# sensor.net
KiCad netlist of a schematic drawn in Altium Designer
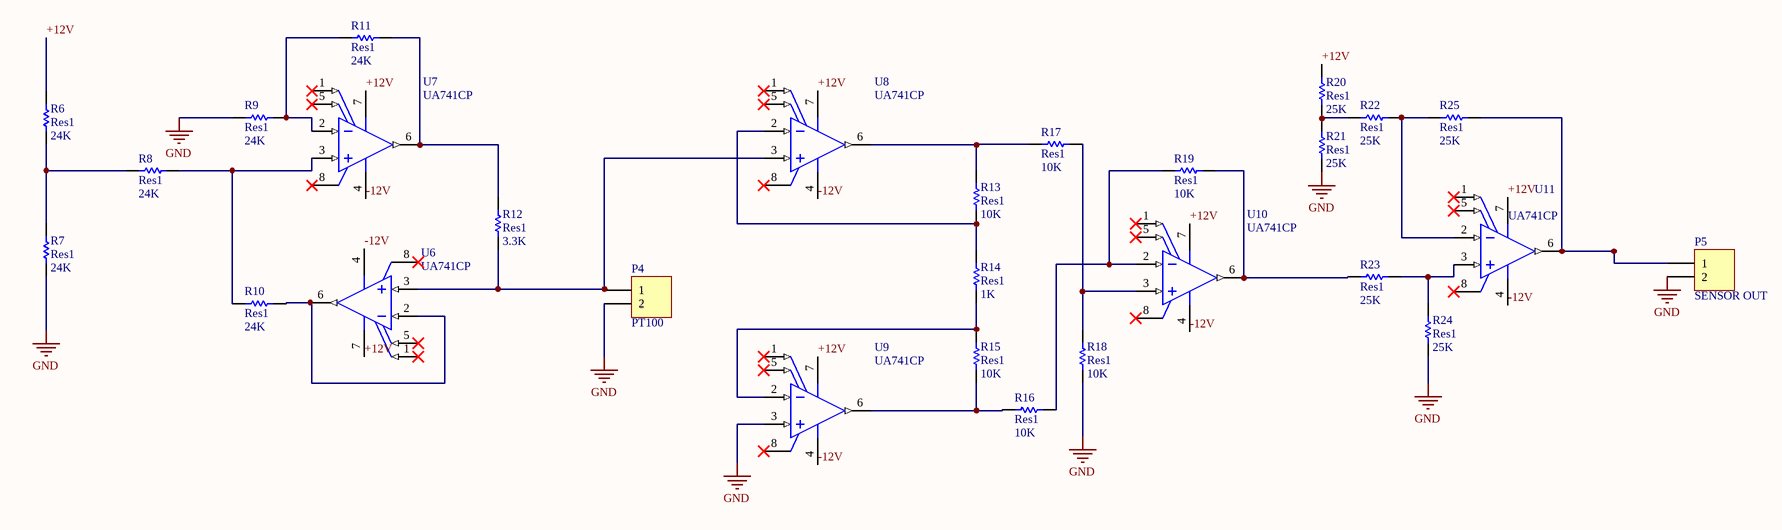
[diagram p0: sensor.SchDoc]

(export (version "E")
  (design (tool "Eeschema 10.0.6"))
  (components
    (comp (ref "P4")
      (value "PT100")
      (footprint "HDR1X2")
      (description "Header, 2-Pin")
      (fields (field (name "PUBLISHER") "Altium Limited"))
      (libsource (lib "Miscellaneous Connectors") (part "Header 2"))
    )
    (comp (ref "P5")
      (value "SENSOR OUT")
      (footprint "HDR1X2")
      (description "Header, 2-Pin")
      (fields (field (name "PUBLISHER") "Altium Limited"))
      (libsource (lib "Miscellaneous Connectors") (part "Header 2"))
    )
    (comp (ref "R6")
      (value "Res1")
      (footprint "AXIAL-0.3")
      (description "Resistor")
      (fields (field (name "ALTIUM_VALUE") "24K") (field (name "PUBLISHER") "Altium Limited"))
      (libsource (lib "Miscellaneous Devices") (part "Res1"))
    )
    (comp (ref "R7")
      (value "Res1")
      (footprint "AXIAL-0.3")
      (description "Resistor")
      (fields (field (name "ALTIUM_VALUE") "24K") (field (name "PUBLISHER") "Altium Limited"))
      (libsource (lib "Miscellaneous Devices") (part "Res1"))
    )
    (comp (ref "R8")
      (value "Res1")
      (footprint "AXIAL-0.3")
      (description "Resistor")
      (fields (field (name "ALTIUM_VALUE") "24K") (field (name "PUBLISHER") "Altium Limited"))
      (libsource (lib "Miscellaneous Devices") (part "Res1"))
    )
    (comp (ref "R9")
      (value "Res1")
      (footprint "AXIAL-0.3")
      (description "Resistor")
      (fields (field (name "ALTIUM_VALUE") "24K") (field (name "PUBLISHER") "Altium Limited"))
      (libsource (lib "Miscellaneous Devices") (part "Res1"))
    )
    (comp (ref "R10")
      (value "Res1")
      (footprint "AXIAL-0.3")
      (description "Resistor")
      (fields (field (name "ALTIUM_VALUE") "24K") (field (name "PUBLISHER") "Altium Limited"))
      (libsource (lib "Miscellaneous Devices") (part "Res1"))
    )
    (comp (ref "R11")
      (value "Res1")
      (footprint "AXIAL-0.3")
      (description "Resistor")
      (fields (field (name "ALTIUM_VALUE") "24K") (field (name "PUBLISHER") "Altium Limited"))
      (libsource (lib "Miscellaneous Devices") (part "Res1"))
    )
    (comp (ref "R12")
      (value "Res1")
      (footprint "AXIAL-0.3")
      (description "Resistor")
      (fields (field (name "ALTIUM_VALUE") "3.3K") (field (name "PUBLISHER") "Altium Limited"))
      (libsource (lib "Miscellaneous Devices") (part "Res1"))
    )
    (comp (ref "R13")
      (value "Res1")
      (footprint "AXIAL-0.3")
      (description "Resistor")
      (fields (field (name "ALTIUM_VALUE") "10K") (field (name "PUBLISHER") "Altium Limited"))
      (libsource (lib "Miscellaneous Devices") (part "Res1"))
    )
    (comp (ref "R14")
      (value "Res1")
      (footprint "AXIAL-0.3")
      (description "Resistor")
      (fields (field (name "ALTIUM_VALUE") "1K") (field (name "PUBLISHER") "Altium Limited"))
      (libsource (lib "Miscellaneous Devices") (part "Res1"))
    )
    (comp (ref "R15")
      (value "Res1")
      (footprint "AXIAL-0.3")
      (description "Resistor")
      (fields (field (name "ALTIUM_VALUE") "10K") (field (name "PUBLISHER") "Altium Limited"))
      (libsource (lib "Miscellaneous Devices") (part "Res1"))
    )
    (comp (ref "R16")
      (value "Res1")
      (footprint "AXIAL-0.3")
      (description "Resistor")
      (fields (field (name "ALTIUM_VALUE") "10K") (field (name "PUBLISHER") "Altium Limited"))
      (libsource (lib "Miscellaneous Devices") (part "Res1"))
    )
    (comp (ref "R17")
      (value "Res1")
      (footprint "AXIAL-0.3")
      (description "Resistor")
      (fields (field (name "ALTIUM_VALUE") "10K") (field (name "PUBLISHER") "Altium Limited"))
      (libsource (lib "Miscellaneous Devices") (part "Res1"))
    )
    (comp (ref "R18")
      (value "Res1")
      (footprint "AXIAL-0.3")
      (description "Resistor")
      (fields (field (name "ALTIUM_VALUE") "10K") (field (name "PUBLISHER") "Altium Limited"))
      (libsource (lib "Miscellaneous Devices") (part "Res1"))
    )
    (comp (ref "R19")
      (value "Res1")
      (footprint "AXIAL-0.3")
      (description "Resistor")
      (fields (field (name "ALTIUM_VALUE") "10K") (field (name "PUBLISHER") "Altium Limited"))
      (libsource (lib "Miscellaneous Devices") (part "Res1"))
    )
    (comp (ref "R20")
      (value "Res1")
      (footprint "AXIAL-0.3")
      (description "Resistor")
      (fields (field (name "ALTIUM_VALUE") "25K") (field (name "PUBLISHER") "Altium Limited"))
      (libsource (lib "Miscellaneous Devices") (part "Res1"))
    )
    (comp (ref "R21")
      (value "Res1")
      (footprint "AXIAL-0.3")
      (description "Resistor")
      (fields (field (name "ALTIUM_VALUE") "25K") (field (name "PUBLISHER") "Altium Limited"))
      (libsource (lib "Miscellaneous Devices") (part "Res1"))
    )
    (comp (ref "R22")
      (value "Res1")
      (footprint "AXIAL-0.3")
      (description "Resistor")
      (fields (field (name "ALTIUM_VALUE") "25K") (field (name "PUBLISHER") "Altium Limited"))
      (libsource (lib "Miscellaneous Devices") (part "Res1"))
    )
    (comp (ref "R23")
      (value "Res1")
      (footprint "AXIAL-0.3")
      (description "Resistor")
      (fields (field (name "ALTIUM_VALUE") "25K") (field (name "PUBLISHER") "Altium Limited"))
      (libsource (lib "Miscellaneous Devices") (part "Res1"))
    )
    (comp (ref "R24")
      (value "Res1")
      (footprint "AXIAL-0.3")
      (description "Resistor")
      (fields (field (name "ALTIUM_VALUE") "25K") (field (name "PUBLISHER") "Altium Limited"))
      (libsource (lib "Miscellaneous Devices") (part "Res1"))
    )
    (comp (ref "R25")
      (value "Res1")
      (footprint "AXIAL-0.3")
      (description "Resistor")
      (fields (field (name "ALTIUM_VALUE") "25K") (field (name "PUBLISHER") "Altium Limited"))
      (libsource (lib "Miscellaneous Devices") (part "Res1"))
    )
    (comp (ref "U6")
      (value "UA741CP")
      (footprint "P0008A")
      (description "General-Purpose Operational Amplifier, 7 to 36 V, 0 to 70 degC, 8-pin DIP (P8), Pb-Free (RoHS)")
      (fields (field (name "MANUFACTURER") "Texas Instruments"))
      (libsource (lib "Altium Content Vault") (part "TI-AMP-S5-2-8"))
    )
    (comp (ref "U7")
      (value "UA741CP")
      (footprint "P0008A")
      (description "General-Purpose Operational Amplifier, 7 to 36 V, 0 to 70 degC, 8-pin DIP (P8), Pb-Free (RoHS)")
      (fields (field (name "MANUFACTURER") "Texas Instruments"))
      (libsource (lib "Altium Content Vault") (part "TI-AMP-S5-2-8"))
    )
    (comp (ref "U8")
      (value "UA741CP")
      (footprint "P0008A")
      (description "General-Purpose Operational Amplifier, 7 to 36 V, 0 to 70 degC, 8-pin DIP (P8), Pb-Free (RoHS)")
      (fields (field (name "MANUFACTURER") "Texas Instruments"))
      (libsource (lib "Altium Content Vault") (part "TI-AMP-S5-2-8"))
    )
    (comp (ref "U9")
      (value "UA741CP")
      (footprint "P0008A")
      (description "General-Purpose Operational Amplifier, 7 to 36 V, 0 to 70 degC, 8-pin DIP (P8), Pb-Free (RoHS)")
      (fields (field (name "MANUFACTURER") "Texas Instruments"))
      (libsource (lib "Altium Content Vault") (part "TI-AMP-S5-2-8"))
    )
    (comp (ref "U10")
      (value "UA741CP")
      (footprint "P0008A")
      (description "General-Purpose Operational Amplifier, 7 to 36 V, 0 to 70 degC, 8-pin DIP (P8), Pb-Free (RoHS)")
      (fields (field (name "MANUFACTURER") "Texas Instruments"))
      (libsource (lib "Altium Content Vault") (part "TI-AMP-S5-2-8"))
    )
    (comp (ref "U11")
      (value "UA741CP")
      (footprint "P0008A")
      (description "General-Purpose Operational Amplifier, 7 to 36 V, 0 to 70 degC, 8-pin DIP (P8), Pb-Free (RoHS)")
      (fields (field (name "MANUFACTURER") "Texas Instruments"))
      (libsource (lib "Altium Content Vault") (part "TI-AMP-S5-2-8"))
    )
  )
  (nets
    (net (code "1") (name "/+12V") (class "Default")
      (node (ref "R20") (pin "2") (pinfunction "2_2") (pintype "passive"))
      (node (ref "R6") (pin "2") (pinfunction "2_2") (pintype "passive"))
      (node (ref "U10") (pin "7") (pinfunction "VCC+_7") (pintype "power_in"))
      (node (ref "U11") (pin "7") (pinfunction "VCC+_7") (pintype "power_in"))
      (node (ref "U6") (pin "7") (pinfunction "VCC+_7") (pintype "power_in"))
      (node (ref "U7") (pin "7") (pinfunction "VCC+_7") (pintype "power_in"))
      (node (ref "U8") (pin "7") (pinfunction "VCC+_7") (pintype "power_in"))
      (node (ref "U9") (pin "7") (pinfunction "VCC+_7") (pintype "power_in"))
    )
    (net (code "2") (name "/-12V") (class "Default")
      (node (ref "U10") (pin "4") (pinfunction "VCC-_4") (pintype "power_in"))
      (node (ref "U11") (pin "4") (pinfunction "VCC-_4") (pintype "power_in"))
      (node (ref "U6") (pin "4") (pinfunction "VCC-_4") (pintype "power_in"))
      (node (ref "U7") (pin "4") (pinfunction "VCC-_4") (pintype "power_in"))
      (node (ref "U8") (pin "4") (pinfunction "VCC-_4") (pintype "power_in"))
      (node (ref "U9") (pin "4") (pinfunction "VCC-_4") (pintype "power_in"))
    )
    (net (code "3") (name "GND") (class "Default")
      (node (ref "P4") (pin "2") (pinfunction "2_2") (pintype "passive"))
      (node (ref "P5") (pin "2") (pinfunction "2_2") (pintype "passive"))
      (node (ref "R18") (pin "2") (pinfunction "2_2") (pintype "passive"))
      (node (ref "R21") (pin "1") (pinfunction "1_1") (pintype "passive"))
      (node (ref "R24") (pin "2") (pinfunction "2_2") (pintype "passive"))
      (node (ref "R7") (pin "1") (pinfunction "1_1") (pintype "passive"))
      (node (ref "R9") (pin "2") (pinfunction "2_2") (pintype "passive"))
      (node (ref "U9") (pin "3") (pinfunction "IN+_3") (pintype "input"))
    )
    (net (code "4") (name "Net-(R6-Pad1)") (class "Default")
      (node (ref "R6") (pin "1") (pinfunction "1_1") (pintype "passive"))
      (node (ref "R7") (pin "2") (pinfunction "2_2") (pintype "passive"))
      (node (ref "R8") (pin "2") (pinfunction "2_2") (pintype "passive"))
    )
    (net (code "5") (name "Net-(R20-Pad1)") (class "Default")
      (node (ref "R20") (pin "1") (pinfunction "1_1") (pintype "passive"))
      (node (ref "R21") (pin "2") (pinfunction "2_2") (pintype "passive"))
      (node (ref "R22") (pin "1") (pinfunction "1_1") (pintype "passive"))
    )
    (net (code "6") (name "Net-(U6-IN+)") (class "Default")
      (node (ref "P4") (pin "1") (pinfunction "1_1") (pintype "passive"))
      (node (ref "R12") (pin "2") (pinfunction "2_2") (pintype "passive"))
      (node (ref "U6") (pin "3") (pinfunction "IN+_3") (pintype "input"))
      (node (ref "U8") (pin "3") (pinfunction "IN+_3") (pintype "input"))
    )
    (net (code "7") (name "Net-(U6-IN-)") (class "Default")
      (node (ref "R10") (pin "1") (pinfunction "1_1") (pintype "passive"))
      (node (ref "U6") (pin "2") (pinfunction "IN-_2") (pintype "input"))
      (node (ref "U6") (pin "6") (pinfunction "OUT_6") (pintype "output"))
    )
    (net (code "8") (name "Net-(U7-IN+)") (class "Default")
      (node (ref "R10") (pin "2") (pinfunction "2_2") (pintype "passive"))
      (node (ref "R8") (pin "1") (pinfunction "1_1") (pintype "passive"))
      (node (ref "U7") (pin "3") (pinfunction "IN+_3") (pintype "input"))
    )
    (net (code "9") (name "Net-(U7-IN-)") (class "Default")
      (node (ref "R11") (pin "2") (pinfunction "2_2") (pintype "passive"))
      (node (ref "R9") (pin "1") (pinfunction "1_1") (pintype "passive"))
      (node (ref "U7") (pin "2") (pinfunction "IN-_2") (pintype "input"))
    )
    (net (code "10") (name "Net-(U7-OUT)") (class "Default")
      (node (ref "R11") (pin "1") (pinfunction "1_1") (pintype "passive"))
      (node (ref "R12") (pin "1") (pinfunction "1_1") (pintype "passive"))
      (node (ref "U7") (pin "6") (pinfunction "OUT_6") (pintype "output"))
    )
    (net (code "11") (name "Net-(U8-IN-)") (class "Default")
      (node (ref "R13") (pin "2") (pinfunction "2_2") (pintype "passive"))
      (node (ref "R14") (pin "1") (pinfunction "1_1") (pintype "passive"))
      (node (ref "U8") (pin "2") (pinfunction "IN-_2") (pintype "input"))
    )
    (net (code "12") (name "Net-(U8-OUT)") (class "Default")
      (node (ref "R13") (pin "1") (pinfunction "1_1") (pintype "passive"))
      (node (ref "R17") (pin "1") (pinfunction "1_1") (pintype "passive"))
      (node (ref "U8") (pin "6") (pinfunction "OUT_6") (pintype "output"))
    )
    (net (code "13") (name "Net-(U9-IN-)") (class "Default")
      (node (ref "R14") (pin "2") (pinfunction "2_2") (pintype "passive"))
      (node (ref "R15") (pin "1") (pinfunction "1_1") (pintype "passive"))
      (node (ref "U9") (pin "2") (pinfunction "IN-_2") (pintype "input"))
    )
    (net (code "14") (name "Net-(U9-OUT)") (class "Default")
      (node (ref "R15") (pin "2") (pinfunction "2_2") (pintype "passive"))
      (node (ref "R16") (pin "1") (pinfunction "1_1") (pintype "passive"))
      (node (ref "U9") (pin "6") (pinfunction "OUT_6") (pintype "output"))
    )
    (net (code "15") (name "Net-(U10-IN+)") (class "Default")
      (node (ref "R17") (pin "2") (pinfunction "2_2") (pintype "passive"))
      (node (ref "R18") (pin "1") (pinfunction "1_1") (pintype "passive"))
      (node (ref "U10") (pin "3") (pinfunction "IN+_3") (pintype "input"))
    )
    (net (code "16") (name "Net-(U10-IN-)") (class "Default")
      (node (ref "R16") (pin "2") (pinfunction "2_2") (pintype "passive"))
      (node (ref "R19") (pin "1") (pinfunction "1_1") (pintype "passive"))
      (node (ref "U10") (pin "2") (pinfunction "IN-_2") (pintype "input"))
    )
    (net (code "17") (name "Net-(U10-OUT)") (class "Default")
      (node (ref "R19") (pin "2") (pinfunction "2_2") (pintype "passive"))
      (node (ref "R23") (pin "1") (pinfunction "1_1") (pintype "passive"))
      (node (ref "U10") (pin "6") (pinfunction "OUT_6") (pintype "output"))
    )
    (net (code "18") (name "Net-(U11-IN+)") (class "Default")
      (node (ref "R23") (pin "2") (pinfunction "2_2") (pintype "passive"))
      (node (ref "R24") (pin "1") (pinfunction "1_1") (pintype "passive"))
      (node (ref "U11") (pin "3") (pinfunction "IN+_3") (pintype "input"))
    )
    (net (code "19") (name "Net-(U11-IN-)") (class "Default")
      (node (ref "R22") (pin "2") (pinfunction "2_2") (pintype "passive"))
      (node (ref "R25") (pin "1") (pinfunction "1_1") (pintype "passive"))
      (node (ref "U11") (pin "2") (pinfunction "IN-_2") (pintype "input"))
    )
    (net (code "20") (name "Net-(U11-OUT)") (class "Default")
      (node (ref "P5") (pin "1") (pinfunction "1_1") (pintype "passive"))
      (node (ref "R25") (pin "2") (pinfunction "2_2") (pintype "passive"))
      (node (ref "U11") (pin "6") (pinfunction "OUT_6") (pintype "output"))
    )
    (net (code "21") (name "unconnected-(U6-NC-Pad8)") (class "Default")
      (node (ref "U6") (pin "8") (pinfunction "NC_8") (pintype "passive+no_connect"))
    )
    (net (code "22") (name "unconnected-(U6-OFFSET_N1-Pad1)") (class "Default")
      (node (ref "U6") (pin "1") (pinfunction "OFFSET_N1_1") (pintype "input+no_connect"))
    )
    (net (code "23") (name "unconnected-(U6-OFFSET_N2-Pad5)") (class "Default")
      (node (ref "U6") (pin "5") (pinfunction "OFFSET_N2_5") (pintype "input+no_connect"))
    )
    (net (code "24") (name "unconnected-(U7-NC-Pad8)") (class "Default")
      (node (ref "U7") (pin "8") (pinfunction "NC_8") (pintype "passive+no_connect"))
    )
    (net (code "25") (name "unconnected-(U7-OFFSET_N1-Pad1)") (class "Default")
      (node (ref "U7") (pin "1") (pinfunction "OFFSET_N1_1") (pintype "input+no_connect"))
    )
    (net (code "26") (name "unconnected-(U7-OFFSET_N2-Pad5)") (class "Default")
      (node (ref "U7") (pin "5") (pinfunction "OFFSET_N2_5") (pintype "input+no_connect"))
    )
    (net (code "27") (name "unconnected-(U8-NC-Pad8)") (class "Default")
      (node (ref "U8") (pin "8") (pinfunction "NC_8") (pintype "passive+no_connect"))
    )
    (net (code "28") (name "unconnected-(U8-OFFSET_N1-Pad1)") (class "Default")
      (node (ref "U8") (pin "1") (pinfunction "OFFSET_N1_1") (pintype "input+no_connect"))
    )
    (net (code "29") (name "unconnected-(U8-OFFSET_N2-Pad5)") (class "Default")
      (node (ref "U8") (pin "5") (pinfunction "OFFSET_N2_5") (pintype "input+no_connect"))
    )
    (net (code "30") (name "unconnected-(U9-NC-Pad8)") (class "Default")
      (node (ref "U9") (pin "8") (pinfunction "NC_8") (pintype "passive+no_connect"))
    )
    (net (code "31") (name "unconnected-(U9-OFFSET_N1-Pad1)") (class "Default")
      (node (ref "U9") (pin "1") (pinfunction "OFFSET_N1_1") (pintype "input+no_connect"))
    )
    (net (code "32") (name "unconnected-(U9-OFFSET_N2-Pad5)") (class "Default")
      (node (ref "U9") (pin "5") (pinfunction "OFFSET_N2_5") (pintype "input+no_connect"))
    )
    (net (code "33") (name "unconnected-(U10-NC-Pad8)") (class "Default")
      (node (ref "U10") (pin "8") (pinfunction "NC_8") (pintype "passive+no_connect"))
    )
    (net (code "34") (name "unconnected-(U10-OFFSET_N1-Pad1)") (class "Default")
      (node (ref "U10") (pin "1") (pinfunction "OFFSET_N1_1") (pintype "input+no_connect"))
    )
    (net (code "35") (name "unconnected-(U10-OFFSET_N2-Pad5)") (class "Default")
      (node (ref "U10") (pin "5") (pinfunction "OFFSET_N2_5") (pintype "input+no_connect"))
    )
    (net (code "36") (name "unconnected-(U11-NC-Pad8)") (class "Default")
      (node (ref "U11") (pin "8") (pinfunction "NC_8") (pintype "passive+no_connect"))
    )
    (net (code "37") (name "unconnected-(U11-OFFSET_N1-Pad1)") (class "Default")
      (node (ref "U11") (pin "1") (pinfunction "OFFSET_N1_1") (pintype "input+no_connect"))
    )
    (net (code "38") (name "unconnected-(U11-OFFSET_N2-Pad5)") (class "Default")
      (node (ref "U11") (pin "5") (pinfunction "OFFSET_N2_5") (pintype "input+no_connect"))
    )
  )
)
